# vdg_voltage_sensor.net
KiCad netlist of a schematic drawn in EAGLE
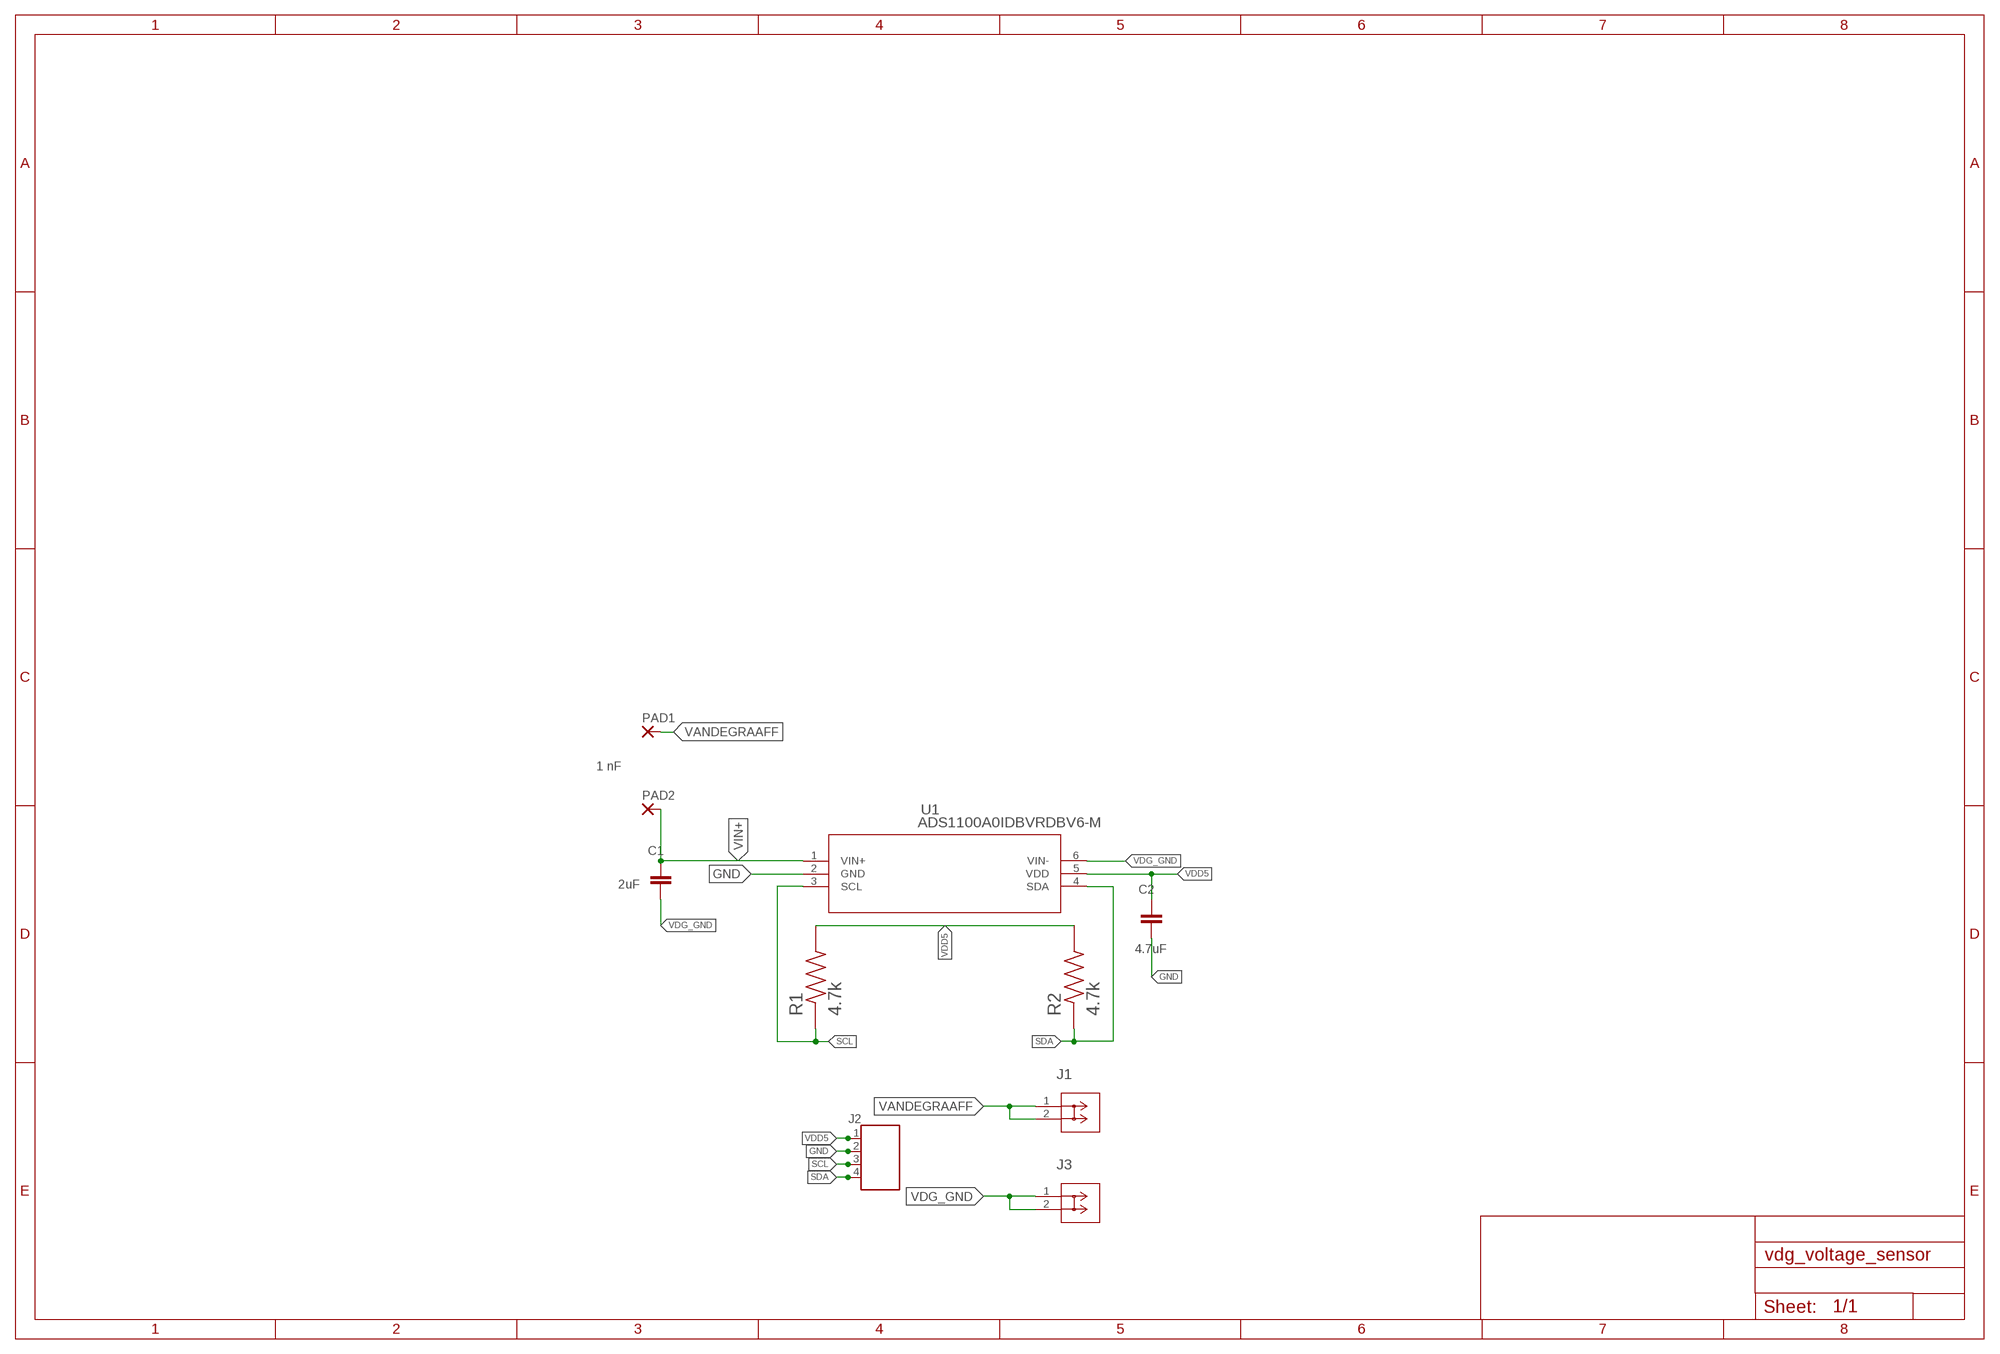
[diagram p0: schematic, sheet 1]

(export (version "E")
  (design (tool "Eeschema 10.0.6"))
  (components
    (comp (ref "C1")
      (value "2uF")
      (footprint "eagle-import:CAP_1206")
      (fields
        (field (name "DIGIKEY_PART_NUMBER") "GRM31CR60J107ME39L")
        (field (name "MANUFACTURER") "Murata Electronics North America")
        (field (name "CREATED_BY") "PCBLayout.com")
      )
      (libsource (lib "eagle-import") (part "GRM31CR60J107ME39L"))
    )
    (comp (ref "C2")
      (value "4.7uF")
      (footprint "eagle-import:CAP_1206")
      (fields
        (field (name "DIGIKEY_PART_NUMBER") "GRM31CR60J107ME39L")
        (field (name "MANUFACTURER") "Murata Electronics North America")
        (field (name "CREATED_BY") "PCBLayout.com")
      )
      (libsource (lib "eagle-import") (part "GRM31CR60J107ME39L"))
    )
    (comp (ref "J1")
      (value "VANDEGRAAFF")
      (footprint "eagle-import:SR99S01VBNN00G7_MZC")
      (fields
        (field (name "MANUFACTURER_PART_NUMBER") "SR99S01VBNN00G7")
        (field (name "COPYRIGHT") "Copyright (C) 2018 Accelerated Designs. All rights reserved")
      )
      (libsource (lib "eagle-import") (part "SR99S01VBNN00G7"))
    )
    (comp (ref "J2")
      (value "691131710004")
      (footprint "eagle-import:691131710004")
      (libsource (lib "eagle-import") (part "691131710004"))
    )
    (comp (ref "J3")
      (value "SR99S01VBNN00G7")
      (footprint "eagle-import:SR99S01VBNN00G7_MZC")
      (fields (field (name "COPYRIGHT") "Copyright (C) 2018 Accelerated Designs. All rights reserved"))
      (libsource (lib "eagle-import") (part "SR99S01VBNN00G7"))
    )
    (comp (ref "PAD1")
      (value "1,6/0,9")
      (footprint "eagle-import:1,6_0,9")
      (libsource (lib "eagle-import") (part "1,6/0,9"))
    )
    (comp (ref "PAD2")
      (value "1,6/0,9")
      (footprint "eagle-import:1,6_0,9")
      (libsource (lib "eagle-import") (part "1,6/0,9"))
    )
    (comp (ref "R1")
      (value "4.7k")
      (footprint "eagle-import:RESC3115X65N")
      (fields
        (field (name "COMMENT") "1-2176328-4")
        (field (name "MF") "TE Connectivity")
        (field (name "MP") "CRGP1206F120R")
      )
      (libsource (lib "eagle-import") (part "CRGP1206F120R"))
    )
    (comp (ref "R2")
      (value "4.7k")
      (footprint "eagle-import:RESC3115X65N")
      (fields
        (field (name "COMMENT") "1-2176328-4")
        (field (name "MF") "TE Connectivity")
        (field (name "MP") "CRGP1206F120R")
      )
      (libsource (lib "eagle-import") (part "CRGP1206F120R"))
    )
    (comp (ref "U1")
      (value "ADS1100A0IDBVRDBV6-M")
      (footprint "eagle-import:DBV6-M")
      (fields
        (field (name "GENERIC_PART_NUMBER") "ADS1100")
        (field (name "MANUFACTURER") "Texas Instruments")
      )
      (libsource (lib "eagle-import") (part "ADS1100A0IDBVRDBV6-M"))
    )
  )
  (nets
    (net (code "1") (name "GND") (class "Default")
      (node (ref "C2") (pin "2") (pinfunction "2_2") (pintype "passive"))
      (node (ref "J2") (pin "2") (pinfunction "2_2") (pintype "passive"))
      (node (ref "U1") (pin "2") (pinfunction "GND_2") (pintype "power_in"))
    )
    (net (code "2") (name "SCL") (class "Default")
      (node (ref "J2") (pin "3") (pinfunction "3_3") (pintype "passive"))
      (node (ref "R1") (pin "1") (pinfunction "1_1") (pintype "passive"))
      (node (ref "U1") (pin "3") (pinfunction "SCL_3") (pintype "passive"))
    )
    (net (code "3") (name "SDA") (class "Default")
      (node (ref "J2") (pin "4") (pinfunction "4_4") (pintype "passive"))
      (node (ref "R2") (pin "1") (pinfunction "1_1") (pintype "passive"))
      (node (ref "U1") (pin "4") (pinfunction "SDA_4") (pintype "passive"))
    )
    (net (code "4") (name "VANDEGRAAFF") (class "Default")
      (node (ref "J1") (pin "1") (pinfunction "1_1") (pintype "passive"))
      (node (ref "J1") (pin "2") (pinfunction "2_2") (pintype "passive"))
      (node (ref "PAD1") (pin "1") (pinfunction "P_1") (pintype "passive"))
    )
    (net (code "5") (name "VDD5") (class "Default")
      (node (ref "C2") (pin "1") (pinfunction "1_1") (pintype "passive"))
      (node (ref "J2") (pin "1") (pinfunction "1_1") (pintype "passive"))
      (node (ref "R1") (pin "2") (pinfunction "2_2") (pintype "passive"))
      (node (ref "R2") (pin "2") (pinfunction "2_2") (pintype "passive"))
      (node (ref "U1") (pin "5") (pinfunction "VDD_5") (pintype "power_in"))
    )
    (net (code "6") (name "VDG_GND") (class "Default")
      (node (ref "C1") (pin "2") (pinfunction "2_2") (pintype "passive"))
      (node (ref "J3") (pin "1") (pinfunction "1_1") (pintype "passive"))
      (node (ref "J3") (pin "2") (pinfunction "2_2") (pintype "passive"))
      (node (ref "U1") (pin "6") (pinfunction "VIN-_6") (pintype "input"))
    )
    (net (code "7") (name "VIN+") (class "Default")
      (node (ref "C1") (pin "1") (pinfunction "1_1") (pintype "passive"))
      (node (ref "PAD2") (pin "1") (pinfunction "P_1") (pintype "passive"))
      (node (ref "U1") (pin "1") (pinfunction "VIN+_1") (pintype "input"))
    )
  )
)
